# Microduino_v1_0.net
KiCad netlist of a schematic drawn in EAGLE
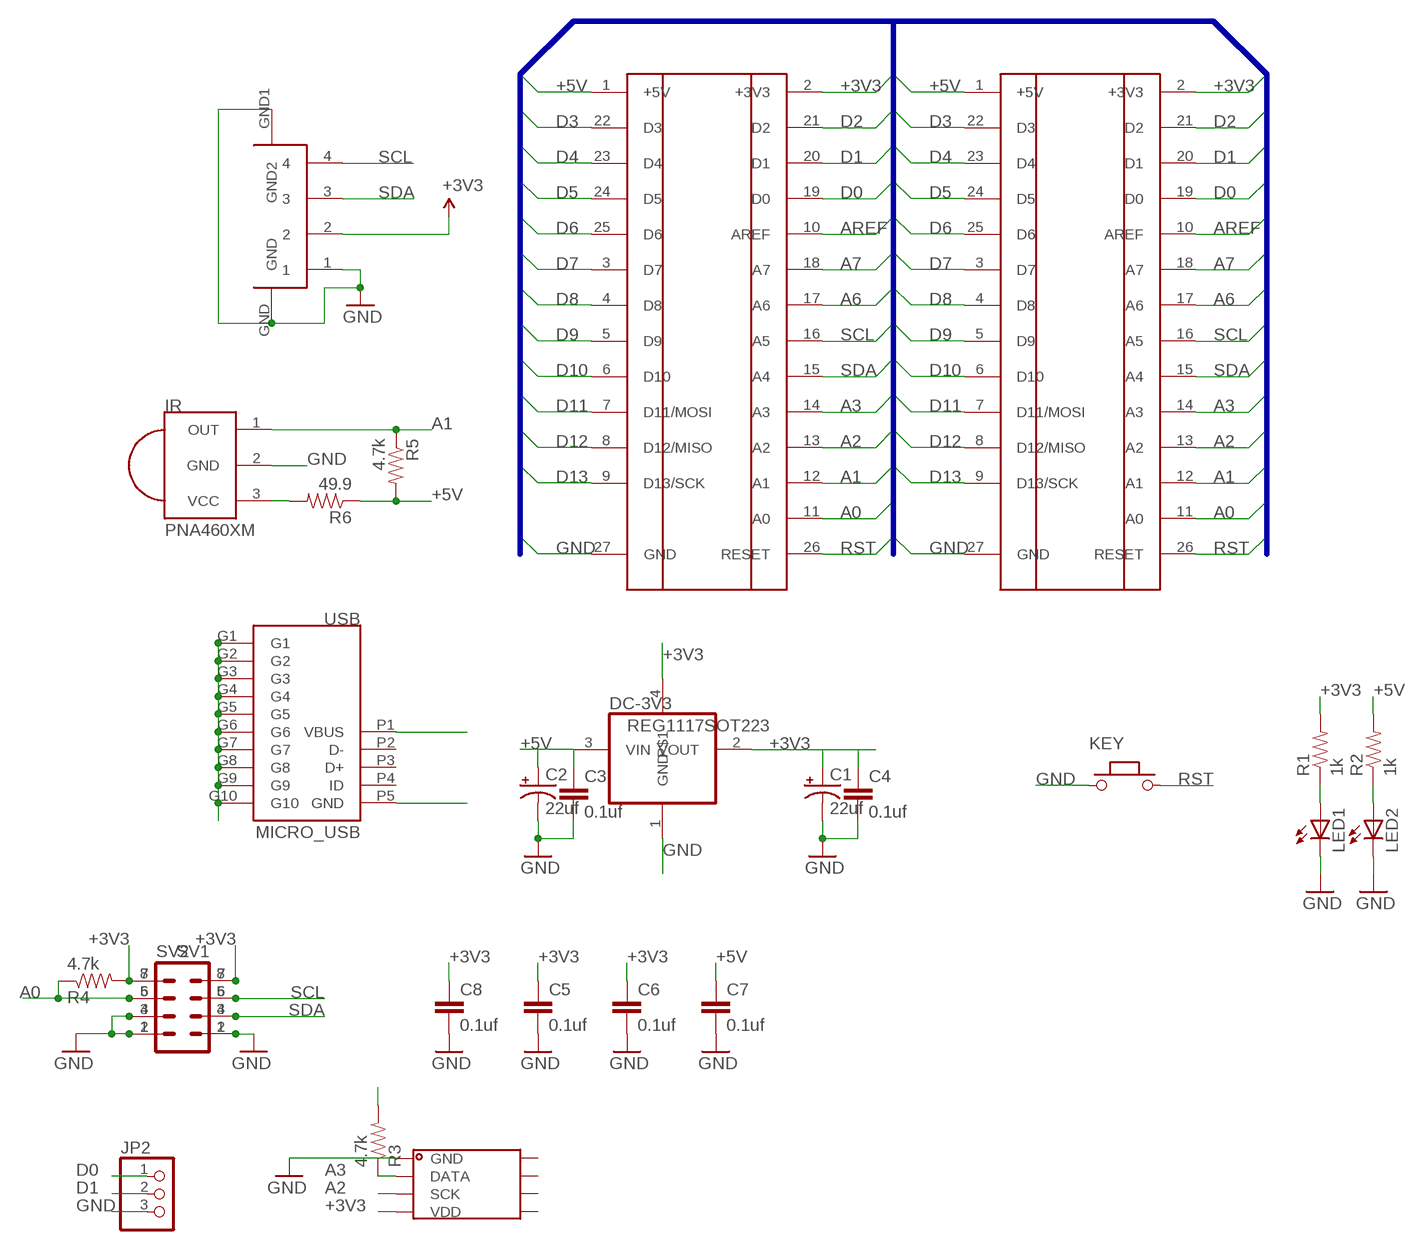
[diagram p0: schematic, sheet 1]

(export (version "E")
  (design (tool "Eeschema 10.0.6"))
  (components
    (comp (ref "C1")
      (value "22uf")
      (footprint "eagle-import:EIA3216")
      (libsource (lib "eagle-import") (part "CAP_POL1206"))
    )
    (comp (ref "C2")
      (value "22uf")
      (footprint "eagle-import:EIA3216")
      (libsource (lib "eagle-import") (part "CAP_POL1206"))
    )
    (comp (ref "C3")
      (value "0.1uf")
      (footprint "eagle-import:0603-CAP")
      (libsource (lib "eagle-import") (part "CAP0603-CAP"))
    )
    (comp (ref "C4")
      (value "0.1uf")
      (footprint "eagle-import:0603-CAP")
      (libsource (lib "eagle-import") (part "CAP0603-CAP"))
    )
    (comp (ref "C5")
      (value "0.1uf")
      (footprint "eagle-import:0603-CAP")
      (libsource (lib "eagle-import") (part "CAP0603-CAP"))
    )
    (comp (ref "C6")
      (value "0.1uf")
      (footprint "eagle-import:0603-CAP")
      (libsource (lib "eagle-import") (part "CAP0603-CAP"))
    )
    (comp (ref "C7")
      (value "0.1uf")
      (footprint "eagle-import:0603-CAP")
      (libsource (lib "eagle-import") (part "CAP0603-CAP"))
    )
    (comp (ref "C8")
      (value "0.1uf")
      (footprint "eagle-import:0603-CAP")
      (libsource (lib "eagle-import") (part "CAP0603-CAP"))
    )
    (comp (ref "DC-3V3")
      (value "REG1117SOT223")
      (footprint "eagle-import:SOT223")
      (libsource (lib "eagle-import") (part "REG1117SOT223"))
    )
    (comp (ref "IR")
      (value "PNA460XM")
      (footprint "eagle-import:PNA460XM")
      (libsource (lib "eagle-import") (part "PNA460XM"))
    )
    (comp (ref "JP2")
      (value "PINHD-1X3")
      (footprint "eagle-import:1X03")
      (libsource (lib "eagle-import") (part "PINHD-1X3"))
    )
    (comp (ref "KEY")
      (value "KEY-TES-018")
      (footprint "eagle-import:KEY-TS-018")
      (libsource (lib "eagle-import") (part "KEY-TES-018"))
    )
    (comp (ref "LED1")
      (value "LED0805")
      (footprint "eagle-import:0805-LED")
      (libsource (lib "eagle-import") (part "LED0805"))
    )
    (comp (ref "LED2")
      (value "LED0805")
      (footprint "eagle-import:0805-LED")
      (libsource (lib "eagle-import") (part "LED0805"))
    )
    (comp (ref "R1")
      (value "1k")
      (footprint "eagle-import:0603-RES")
      (libsource (lib "eagle-import") (part "RESISTOR0603-RES"))
    )
    (comp (ref "R2")
      (value "1k")
      (footprint "eagle-import:0603-RES")
      (libsource (lib "eagle-import") (part "RESISTOR0603-RES"))
    )
    (comp (ref "R3")
      (value "4.7k")
      (footprint "eagle-import:0603-RES")
      (libsource (lib "eagle-import") (part "MY_RESISTOR0603-RES"))
    )
    (comp (ref "R4")
      (value "4.7k")
      (footprint "eagle-import:0603-RES")
      (libsource (lib "eagle-import") (part "MY_RESISTOR0603-RES"))
    )
    (comp (ref "R5")
      (value "4.7k")
      (footprint "eagle-import:0603-RES")
      (libsource (lib "eagle-import") (part "MY_RESISTOR0603-RES"))
    )
    (comp (ref "R6")
      (value "49.9")
      (footprint "eagle-import:0603-RES")
      (libsource (lib "eagle-import") (part "MY_RESISTOR0603-RES"))
    )
    (comp (ref "SV1")
      (value "MA04-2")
      (footprint "eagle-import:MA04-2")
      (fields (field (name "OC_FARNELL") "unknown") (field (name "OC_NEWARK") "unknown"))
      (libsource (lib "eagle-import") (part "MA04-2"))
    )
    (comp (ref "SV2")
      (value "MA04-2")
      (footprint "eagle-import:MA04-2")
      (fields (field (name "OC_FARNELL") "unknown") (field (name "OC_NEWARK") "unknown"))
      (libsource (lib "eagle-import") (part "MA04-2"))
    )
    (comp (ref "U$1")
      (value "PING-MICRDUINO/1009+")
      (footprint "eagle-import:PIN-MICRODUINO-1009")
      (libsource (lib "eagle-import") (part "PING-MICRDUINO/1009"))
    )
    (comp (ref "U$2")
      (value "PING-MICRDUINO/1009+")
      (footprint "eagle-import:PIN-MICRODUINO-1009")
      (libsource (lib "eagle-import") (part "PING-MICRDUINO/1009"))
    )
    (comp (ref "U$3")
      (value "S4B-XH-SM4-TB")
      (footprint "eagle-import:XH-SM4-TB")
      (libsource (lib "eagle-import") (part "S4B-XH-SM4-TB"))
    )
    (comp (ref "U$4")
      (value "SHT11")
      (footprint "eagle-import:SHT11")
      (libsource (lib "eagle-import") (part "SHT11"))
    )
    (comp (ref "USB")
      (value "MICRO_USB")
      (footprint "eagle-import:MICRO_USB_LJ")
      (libsource (lib "eagle-import") (part "MICRO_USB"))
    )
  )
  (nets
    (net (code "1") (name "+3V3") (class "Default")
      (node (ref "C1") (pin "A") (pinfunction "+_A") (pintype "passive"))
      (node (ref "C4") (pin "1") (pinfunction "1_1") (pintype "passive"))
      (node (ref "C5") (pin "1") (pinfunction "1_1") (pintype "passive"))
      (node (ref "C6") (pin "1") (pinfunction "1_1") (pintype "passive"))
      (node (ref "C8") (pin "1") (pinfunction "1_1") (pintype "passive"))
      (node (ref "DC-3V3") (pin "2") (pinfunction "VOUT_2") (pintype "output"))
      (node (ref "DC-3V3") (pin "4") (pinfunction "P$1_4") (pintype "bidirectional"))
      (node (ref "R1") (pin "2") (pinfunction "2_2") (pintype "passive"))
      (node (ref "R3") (pin "2") (pinfunction "2_2") (pintype "passive"))
      (node (ref "R4") (pin "2") (pinfunction "2_2") (pintype "passive"))
      (node (ref "SV1") (pin "7") (pinfunction "7_7") (pintype "passive"))
      (node (ref "SV1") (pin "8") (pinfunction "8_8") (pintype "passive"))
      (node (ref "SV2") (pin "7") (pinfunction "7_7") (pintype "passive"))
      (node (ref "SV2") (pin "8") (pinfunction "8_8") (pintype "passive"))
      (node (ref "U$1") (pin "2") (pinfunction "+3V3_2") (pintype "bidirectional"))
      (node (ref "U$2") (pin "2") (pinfunction "+3V3_2") (pintype "bidirectional"))
      (node (ref "U$3") (pin "2") (pinfunction "2_2") (pintype "bidirectional"))
      (node (ref "U$4") (pin "4") (pinfunction "VDD_4") (pintype "bidirectional"))
    )
    (net (code "2") (name "/+5V") (class "Default")
      (node (ref "C2") (pin "A") (pinfunction "+_A") (pintype "passive"))
      (node (ref "C3") (pin "1") (pinfunction "1_1") (pintype "passive"))
      (node (ref "C7") (pin "1") (pinfunction "1_1") (pintype "passive"))
      (node (ref "DC-3V3") (pin "3") (pinfunction "VIN_3") (pintype "input"))
      (node (ref "R2") (pin "2") (pinfunction "2_2") (pintype "passive"))
      (node (ref "R5") (pin "2") (pinfunction "2_2") (pintype "passive"))
      (node (ref "R6") (pin "1") (pinfunction "1_1") (pintype "passive"))
      (node (ref "U$1") (pin "1") (pinfunction "+5V_1") (pintype "bidirectional"))
      (node (ref "U$2") (pin "1") (pinfunction "+5V_1") (pintype "bidirectional"))
      (node (ref "USB") (pin "P1") (pinfunction "VBUS_P1") (pintype "power_in"))
    )
    (net (code "3") (name "/A0") (class "Default")
      (node (ref "R4") (pin "1") (pinfunction "1_1") (pintype "passive"))
      (node (ref "SV1") (pin "5") (pinfunction "5_5") (pintype "passive"))
      (node (ref "SV2") (pin "6") (pinfunction "6_6") (pintype "passive"))
      (node (ref "U$1") (pin "11") (pinfunction "A0_11") (pintype "bidirectional"))
      (node (ref "U$2") (pin "11") (pinfunction "A0_11") (pintype "bidirectional"))
    )
    (net (code "4") (name "/A1") (class "Default")
      (node (ref "IR") (pin "1") (pinfunction "OUT_1") (pintype "output"))
      (node (ref "R5") (pin "1") (pinfunction "1_1") (pintype "passive"))
      (node (ref "U$1") (pin "12") (pinfunction "A1_12") (pintype "bidirectional"))
      (node (ref "U$2") (pin "12") (pinfunction "A1_12") (pintype "bidirectional"))
    )
    (net (code "5") (name "/A2") (class "Default")
      (node (ref "U$1") (pin "13") (pinfunction "A2_13") (pintype "bidirectional"))
      (node (ref "U$2") (pin "13") (pinfunction "A2_13") (pintype "bidirectional"))
      (node (ref "U$4") (pin "3") (pinfunction "SCK_3") (pintype "bidirectional"))
    )
    (net (code "6") (name "/A3") (class "Default")
      (node (ref "R3") (pin "1") (pinfunction "1_1") (pintype "passive"))
      (node (ref "U$1") (pin "14") (pinfunction "A3_14") (pintype "bidirectional"))
      (node (ref "U$2") (pin "14") (pinfunction "A3_14") (pintype "bidirectional"))
      (node (ref "U$4") (pin "2") (pinfunction "DATA_2") (pintype "bidirectional"))
    )
    (net (code "7") (name "/A6") (class "Default")
      (node (ref "U$1") (pin "17") (pinfunction "A6_17") (pintype "bidirectional"))
      (node (ref "U$2") (pin "17") (pinfunction "A6_17") (pintype "bidirectional"))
    )
    (net (code "8") (name "/A7") (class "Default")
      (node (ref "U$1") (pin "18") (pinfunction "A7_18") (pintype "bidirectional"))
      (node (ref "U$2") (pin "18") (pinfunction "A7_18") (pintype "bidirectional"))
    )
    (net (code "9") (name "/AREF") (class "Default")
      (node (ref "U$1") (pin "10") (pinfunction "AREF_10") (pintype "bidirectional"))
      (node (ref "U$2") (pin "10") (pinfunction "AREF_10") (pintype "bidirectional"))
    )
    (net (code "10") (name "/D0") (class "Default")
      (node (ref "JP2") (pin "1") (pinfunction "1_1") (pintype "passive"))
      (node (ref "U$1") (pin "19") (pinfunction "D0_19") (pintype "bidirectional"))
      (node (ref "U$2") (pin "19") (pinfunction "D0_19") (pintype "bidirectional"))
    )
    (net (code "11") (name "/D1") (class "Default")
      (node (ref "JP2") (pin "2") (pinfunction "2_2") (pintype "passive"))
      (node (ref "U$1") (pin "20") (pinfunction "D1_20") (pintype "bidirectional"))
      (node (ref "U$2") (pin "20") (pinfunction "D1_20") (pintype "bidirectional"))
    )
    (net (code "12") (name "/D2") (class "Default")
      (node (ref "U$1") (pin "21") (pinfunction "D2_21") (pintype "bidirectional"))
      (node (ref "U$2") (pin "21") (pinfunction "D2_21") (pintype "bidirectional"))
    )
    (net (code "13") (name "/D3") (class "Default")
      (node (ref "U$1") (pin "22") (pinfunction "D3_22") (pintype "bidirectional"))
      (node (ref "U$2") (pin "22") (pinfunction "D3_22") (pintype "bidirectional"))
    )
    (net (code "14") (name "/D4") (class "Default")
      (node (ref "U$1") (pin "23") (pinfunction "D4_23") (pintype "bidirectional"))
      (node (ref "U$2") (pin "23") (pinfunction "D4_23") (pintype "bidirectional"))
    )
    (net (code "15") (name "/D5") (class "Default")
      (node (ref "U$1") (pin "24") (pinfunction "D5_24") (pintype "bidirectional"))
      (node (ref "U$2") (pin "24") (pinfunction "D5_24") (pintype "bidirectional"))
    )
    (net (code "16") (name "/D6") (class "Default")
      (node (ref "U$1") (pin "25") (pinfunction "D6_25") (pintype "bidirectional"))
      (node (ref "U$2") (pin "25") (pinfunction "D6_25") (pintype "bidirectional"))
    )
    (net (code "17") (name "/D7") (class "Default")
      (node (ref "U$1") (pin "3") (pinfunction "D7_3") (pintype "bidirectional"))
      (node (ref "U$2") (pin "3") (pinfunction "D7_3") (pintype "bidirectional"))
    )
    (net (code "18") (name "/D8") (class "Default")
      (node (ref "U$1") (pin "4") (pinfunction "D8_4") (pintype "bidirectional"))
      (node (ref "U$2") (pin "4") (pinfunction "D8_4") (pintype "bidirectional"))
    )
    (net (code "19") (name "/D9") (class "Default")
      (node (ref "U$1") (pin "5") (pinfunction "D9_5") (pintype "bidirectional"))
      (node (ref "U$2") (pin "5") (pinfunction "D9_5") (pintype "bidirectional"))
    )
    (net (code "20") (name "/D10") (class "Default")
      (node (ref "U$1") (pin "6") (pinfunction "D10_6") (pintype "bidirectional"))
      (node (ref "U$2") (pin "6") (pinfunction "D10_6") (pintype "bidirectional"))
    )
    (net (code "21") (name "/D11") (class "Default")
      (node (ref "U$1") (pin "7") (pinfunction "D11/MOSI_7") (pintype "bidirectional"))
      (node (ref "U$2") (pin "7") (pinfunction "D11/MOSI_7") (pintype "bidirectional"))
    )
    (net (code "22") (name "/D12") (class "Default")
      (node (ref "U$1") (pin "8") (pinfunction "D12/MISO_8") (pintype "bidirectional"))
      (node (ref "U$2") (pin "8") (pinfunction "D12/MISO_8") (pintype "bidirectional"))
    )
    (net (code "23") (name "/D13") (class "Default")
      (node (ref "U$1") (pin "9") (pinfunction "D13/SCK_9") (pintype "bidirectional"))
      (node (ref "U$2") (pin "9") (pinfunction "D13/SCK_9") (pintype "bidirectional"))
    )
    (net (code "24") (name "/RST") (class "Default")
      (node (ref "KEY") (pin "1") (pinfunction "2_1") (pintype "bidirectional"))
      (node (ref "U$1") (pin "26") (pinfunction "RESET_26") (pintype "bidirectional"))
      (node (ref "U$2") (pin "26") (pinfunction "RESET_26") (pintype "bidirectional"))
    )
    (net (code "25") (name "/SCL") (class "Default")
      (node (ref "SV1") (pin "6") (pinfunction "6_6") (pintype "passive"))
      (node (ref "SV2") (pin "5") (pinfunction "5_5") (pintype "passive"))
      (node (ref "U$1") (pin "16") (pinfunction "A5_16") (pintype "bidirectional"))
      (node (ref "U$2") (pin "16") (pinfunction "A5_16") (pintype "bidirectional"))
      (node (ref "U$3") (pin "4") (pinfunction "4_4") (pintype "bidirectional"))
    )
    (net (code "26") (name "/SDA") (class "Default")
      (node (ref "SV1") (pin "4") (pinfunction "4_4") (pintype "passive"))
      (node (ref "SV2") (pin "3") (pinfunction "3_3") (pintype "passive"))
      (node (ref "U$1") (pin "15") (pinfunction "A4_15") (pintype "bidirectional"))
      (node (ref "U$2") (pin "15") (pinfunction "A4_15") (pintype "bidirectional"))
      (node (ref "U$3") (pin "3") (pinfunction "3_3") (pintype "bidirectional"))
    )
    (net (code "27") (name "GND") (class "Default")
      (node (ref "C1") (pin "C") (pinfunction "-_C") (pintype "passive"))
      (node (ref "C2") (pin "C") (pinfunction "-_C") (pintype "passive"))
      (node (ref "C3") (pin "2") (pinfunction "2_2") (pintype "passive"))
      (node (ref "C4") (pin "2") (pinfunction "2_2") (pintype "passive"))
      (node (ref "C5") (pin "2") (pinfunction "2_2") (pintype "passive"))
      (node (ref "C6") (pin "2") (pinfunction "2_2") (pintype "passive"))
      (node (ref "C7") (pin "2") (pinfunction "2_2") (pintype "passive"))
      (node (ref "C8") (pin "2") (pinfunction "2_2") (pintype "passive"))
      (node (ref "DC-3V3") (pin "1") (pinfunction "GND_1") (pintype "power_in"))
      (node (ref "IR") (pin "2") (pinfunction "GND_2") (pintype "power_in"))
      (node (ref "JP2") (pin "3") (pinfunction "3_3") (pintype "passive"))
      (node (ref "KEY") (pin "2") (pinfunction "1_2") (pintype "bidirectional"))
      (node (ref "LED1") (pin "C") (pinfunction "C_C") (pintype "passive"))
      (node (ref "LED2") (pin "C") (pinfunction "C_C") (pintype "passive"))
      (node (ref "SV1") (pin "1") (pinfunction "1_1") (pintype "passive"))
      (node (ref "SV1") (pin "2") (pinfunction "2_2") (pintype "passive"))
      (node (ref "SV1") (pin "3") (pinfunction "3_3") (pintype "passive"))
      (node (ref "SV2") (pin "1") (pinfunction "1_1") (pintype "passive"))
      (node (ref "SV2") (pin "2") (pinfunction "2_2") (pintype "passive"))
      (node (ref "SV2") (pin "4") (pinfunction "4_4") (pintype "passive"))
      (node (ref "U$1") (pin "27") (pinfunction "GND_27") (pintype "bidirectional"))
      (node (ref "U$2") (pin "27") (pinfunction "GND_27") (pintype "bidirectional"))
      (node (ref "U$3") (pin "1") (pinfunction "1_1") (pintype "bidirectional"))
      (node (ref "U$3") (pin "GND") (pinfunction "GND_GND") (pintype "bidirectional"))
      (node (ref "U$3") (pin "GND1") (pinfunction "GND2_GND1") (pintype "bidirectional"))
      (node (ref "U$4") (pin "1") (pinfunction "GND_1") (pintype "bidirectional"))
      (node (ref "USB") (pin "G1") (pinfunction "G1_G1") (pintype "bidirectional"))
      (node (ref "USB") (pin "G10") (pinfunction "G10_G10") (pintype "passive"))
      (node (ref "USB") (pin "G2") (pinfunction "G2_G2") (pintype "bidirectional"))
      (node (ref "USB") (pin "G3") (pinfunction "G3_G3") (pintype "bidirectional"))
      (node (ref "USB") (pin "G4") (pinfunction "G4_G4") (pintype "bidirectional"))
      (node (ref "USB") (pin "G5") (pinfunction "G5_G5") (pintype "bidirectional"))
      (node (ref "USB") (pin "G6") (pinfunction "G6_G6") (pintype "bidirectional"))
      (node (ref "USB") (pin "G7") (pinfunction "G7_G7") (pintype "passive"))
      (node (ref "USB") (pin "G8") (pinfunction "G8_G8") (pintype "passive"))
      (node (ref "USB") (pin "G9") (pinfunction "G9_G9") (pintype "passive"))
      (node (ref "USB") (pin "P5") (pinfunction "GND_P5") (pintype "passive"))
    )
    (net (code "28") (name "Net-(IR-VCC)") (class "Default")
      (node (ref "IR") (pin "3") (pinfunction "VCC_3") (pintype "power_in"))
      (node (ref "R6") (pin "2") (pinfunction "2_2") (pintype "passive"))
    )
    (net (code "29") (name "Net-(LED1-PadA)") (class "Default")
      (node (ref "LED1") (pin "A") (pinfunction "A_A") (pintype "passive"))
      (node (ref "R1") (pin "1") (pinfunction "1_1") (pintype "passive"))
    )
    (net (code "30") (name "Net-(LED2-PadA)") (class "Default")
      (node (ref "LED2") (pin "A") (pinfunction "A_A") (pintype "passive"))
      (node (ref "R2") (pin "1") (pinfunction "1_1") (pintype "passive"))
    )
    (net (code "31") (name "unconnected-(U$4-PadP$5)") (class "Default")
      (node (ref "U$4") (pin "P$5") (pinfunction "P$5_P$5") (pintype "bidirectional"))
    )
    (net (code "32") (name "unconnected-(U$4-PadP$6)") (class "Default")
      (node (ref "U$4") (pin "P$6") (pinfunction "P$6_P$6") (pintype "bidirectional"))
    )
    (net (code "33") (name "unconnected-(U$4-PadP$7)") (class "Default")
      (node (ref "U$4") (pin "P$7") (pinfunction "P$7_P$7") (pintype "bidirectional"))
    )
    (net (code "34") (name "unconnected-(U$4-PadP$8)") (class "Default")
      (node (ref "U$4") (pin "P$8") (pinfunction "P$8_P$8") (pintype "bidirectional"))
    )
    (net (code "35") (name "unconnected-(USB-D+-PadP3)") (class "Default")
      (node (ref "USB") (pin "P3") (pinfunction "D+_P3") (pintype "bidirectional"))
    )
    (net (code "36") (name "unconnected-(USB-D--PadP2)") (class "Default")
      (node (ref "USB") (pin "P2") (pinfunction "D-_P2") (pintype "bidirectional"))
    )
    (net (code "37") (name "unconnected-(USB-ID-PadP4)") (class "Default")
      (node (ref "USB") (pin "P4") (pinfunction "ID_P4") (pintype "bidirectional"))
    )
  )
)
